# line_sensor.net
KiCad netlist of a schematic drawn in EAGLE
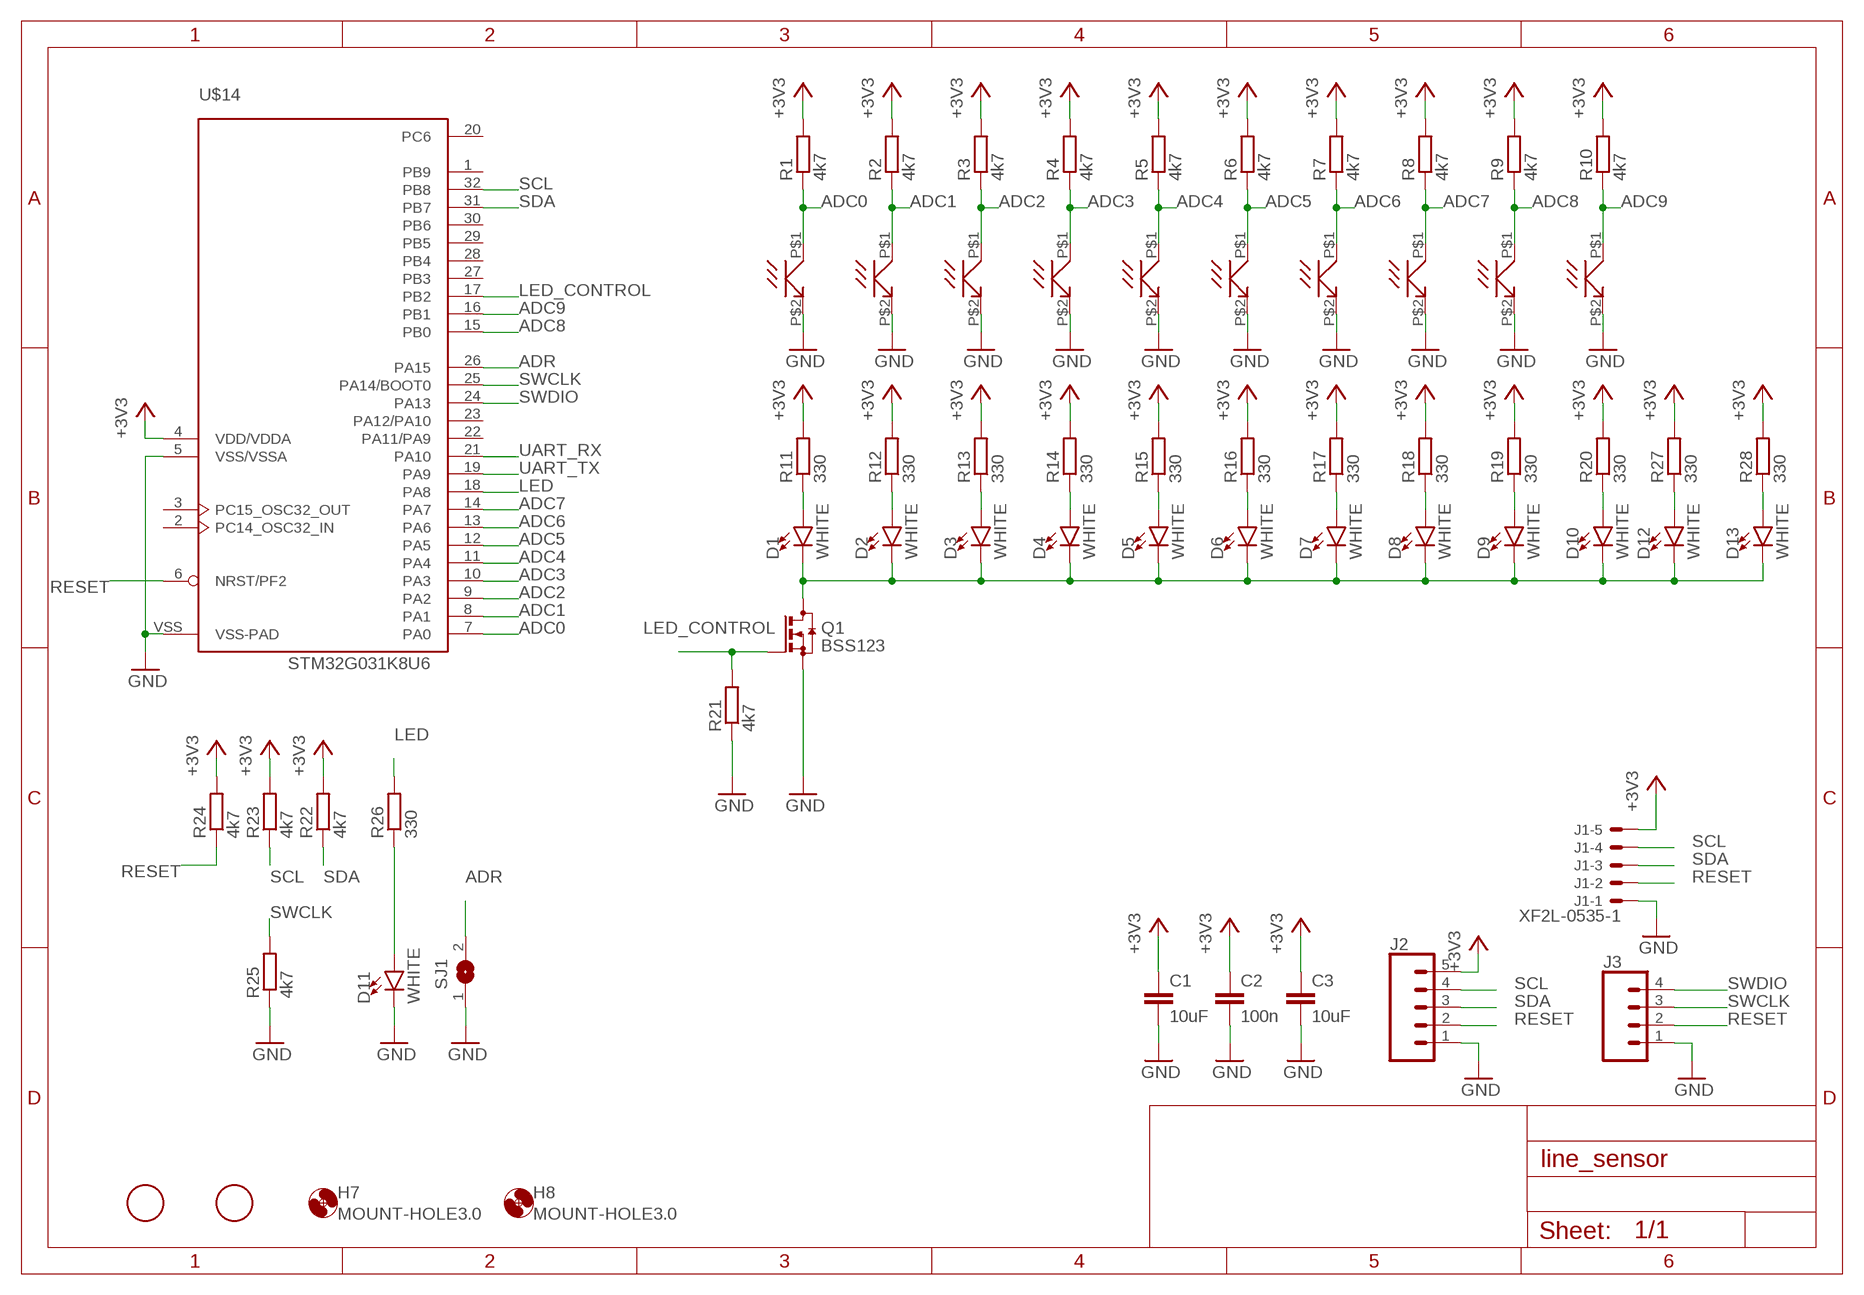
[diagram p0: schematic, sheet 1]

(export (version "E")
  (design (tool "Eeschema 10.0.6"))
  (components
    (comp (ref "C1")
      (value "10uF")
      (footprint "eagle-import:C0805K")
      (libsource (lib "eagle-import") (part "C-EUC0805K"))
    )
    (comp (ref "C2")
      (value "100n")
      (footprint "eagle-import:C0805K")
      (libsource (lib "eagle-import") (part "C-EUC0805K"))
    )
    (comp (ref "C3")
      (value "10uF")
      (footprint "eagle-import:C0805K")
      (libsource (lib "eagle-import") (part "C-EUC0805K"))
    )
    (comp (ref "D1")
      (value "WHITE")
      (footprint "eagle-import:LED-1206")
      (libsource (lib "eagle-import") (part "LED-WHITE1206"))
    )
    (comp (ref "D2")
      (value "WHITE")
      (footprint "eagle-import:LED-1206")
      (libsource (lib "eagle-import") (part "LED-WHITE1206"))
    )
    (comp (ref "D3")
      (value "WHITE")
      (footprint "eagle-import:LED-1206")
      (libsource (lib "eagle-import") (part "LED-WHITE1206"))
    )
    (comp (ref "D4")
      (value "WHITE")
      (footprint "eagle-import:LED-1206")
      (libsource (lib "eagle-import") (part "LED-WHITE1206"))
    )
    (comp (ref "D5")
      (value "WHITE")
      (footprint "eagle-import:LED-1206")
      (libsource (lib "eagle-import") (part "LED-WHITE1206"))
    )
    (comp (ref "D6")
      (value "WHITE")
      (footprint "eagle-import:LED-1206")
      (libsource (lib "eagle-import") (part "LED-WHITE1206"))
    )
    (comp (ref "D7")
      (value "WHITE")
      (footprint "eagle-import:LED-1206")
      (libsource (lib "eagle-import") (part "LED-WHITE1206"))
    )
    (comp (ref "D8")
      (value "WHITE")
      (footprint "eagle-import:LED-1206")
      (libsource (lib "eagle-import") (part "LED-WHITE1206"))
    )
    (comp (ref "D9")
      (value "WHITE")
      (footprint "eagle-import:LED-1206")
      (libsource (lib "eagle-import") (part "LED-WHITE1206"))
    )
    (comp (ref "D10")
      (value "WHITE")
      (footprint "eagle-import:LED-1206")
      (libsource (lib "eagle-import") (part "LED-WHITE1206"))
    )
    (comp (ref "D11")
      (value "WHITE")
      (footprint "eagle-import:LED-1206")
      (libsource (lib "eagle-import") (part "LED-WHITE1206"))
    )
    (comp (ref "D12")
      (value "WHITE")
      (footprint "eagle-import:LED-1206")
      (libsource (lib "eagle-import") (part "LED-WHITE1206"))
    )
    (comp (ref "D13")
      (value "WHITE")
      (footprint "eagle-import:LED-1206")
      (libsource (lib "eagle-import") (part "LED-WHITE1206"))
    )
    (comp (ref "H7")
      (value "MOUNT-HOLE3.0")
      (footprint "eagle-import:3,0")
      (libsource (lib "eagle-import") (part "MOUNT-HOLE3.0"))
    )
    (comp (ref "H8")
      (value "MOUNT-HOLE3.0")
      (footprint "eagle-import:3,0")
      (libsource (lib "eagle-import") (part "MOUNT-HOLE3.0"))
    )
    (comp (ref "J1")
      (value "XF2L-0535-1")
      (footprint "eagle-import:XF2L-0535-1")
      (fields (field (name "MPN") "XF2L-0535-1A"))
      (libsource (lib "eagle-import") (part "XF2-05?35-1L"))
    )
    (comp (ref "J2")
      (value "CONN_05")
      (footprint "eagle-import:1X05")
      (libsource (lib "eagle-import") (part "CONN_05"))
    )
    (comp (ref "J3")
      (value "CONN_04LOCK")
      (footprint "eagle-import:1X04_LOCK")
      (libsource (lib "eagle-import") (part "CONN_04LOCK"))
    )
    (comp (ref "Q1")
      (value "BSS123")
      (footprint "eagle-import:SOT23")
      (libsource (lib "eagle-import") (part "BSS123"))
    )
    (comp (ref "R1")
      (value "4k7")
      (footprint "eagle-import:M0805")
      (libsource (lib "eagle-import") (part "R-EU_M0805"))
    )
    (comp (ref "R2")
      (value "4k7")
      (footprint "eagle-import:M0805")
      (libsource (lib "eagle-import") (part "R-EU_M0805"))
    )
    (comp (ref "R3")
      (value "4k7")
      (footprint "eagle-import:M0805")
      (libsource (lib "eagle-import") (part "R-EU_M0805"))
    )
    (comp (ref "R4")
      (value "4k7")
      (footprint "eagle-import:M0805")
      (libsource (lib "eagle-import") (part "R-EU_M0805"))
    )
    (comp (ref "R5")
      (value "4k7")
      (footprint "eagle-import:M0805")
      (libsource (lib "eagle-import") (part "R-EU_M0805"))
    )
    (comp (ref "R6")
      (value "4k7")
      (footprint "eagle-import:M0805")
      (libsource (lib "eagle-import") (part "R-EU_M0805"))
    )
    (comp (ref "R7")
      (value "4k7")
      (footprint "eagle-import:M0805")
      (libsource (lib "eagle-import") (part "R-EU_M0805"))
    )
    (comp (ref "R8")
      (value "4k7")
      (footprint "eagle-import:M0805")
      (libsource (lib "eagle-import") (part "R-EU_M0805"))
    )
    (comp (ref "R9")
      (value "4k7")
      (footprint "eagle-import:M0805")
      (libsource (lib "eagle-import") (part "R-EU_M0805"))
    )
    (comp (ref "R10")
      (value "4k7")
      (footprint "eagle-import:M0805")
      (libsource (lib "eagle-import") (part "R-EU_M0805"))
    )
    (comp (ref "R11")
      (value "330")
      (footprint "eagle-import:M0805")
      (libsource (lib "eagle-import") (part "R-EU_M0805"))
    )
    (comp (ref "R12")
      (value "330")
      (footprint "eagle-import:M0805")
      (libsource (lib "eagle-import") (part "R-EU_M0805"))
    )
    (comp (ref "R13")
      (value "330")
      (footprint "eagle-import:M0805")
      (libsource (lib "eagle-import") (part "R-EU_M0805"))
    )
    (comp (ref "R14")
      (value "330")
      (footprint "eagle-import:M0805")
      (libsource (lib "eagle-import") (part "R-EU_M0805"))
    )
    (comp (ref "R15")
      (value "330")
      (footprint "eagle-import:M0805")
      (libsource (lib "eagle-import") (part "R-EU_M0805"))
    )
    (comp (ref "R16")
      (value "330")
      (footprint "eagle-import:M0805")
      (libsource (lib "eagle-import") (part "R-EU_M0805"))
    )
    (comp (ref "R17")
      (value "330")
      (footprint "eagle-import:M0805")
      (libsource (lib "eagle-import") (part "R-EU_M0805"))
    )
    (comp (ref "R18")
      (value "330")
      (footprint "eagle-import:M0805")
      (libsource (lib "eagle-import") (part "R-EU_M0805"))
    )
    (comp (ref "R19")
      (value "330")
      (footprint "eagle-import:M0805")
      (libsource (lib "eagle-import") (part "R-EU_M0805"))
    )
    (comp (ref "R20")
      (value "330")
      (footprint "eagle-import:M0805")
      (libsource (lib "eagle-import") (part "R-EU_M0805"))
    )
    (comp (ref "R21")
      (value "4k7")
      (footprint "eagle-import:M0805")
      (libsource (lib "eagle-import") (part "R-EU_M0805"))
    )
    (comp (ref "R22")
      (value "4k7")
      (footprint "eagle-import:M0805")
      (libsource (lib "eagle-import") (part "R-EU_M0805"))
    )
    (comp (ref "R23")
      (value "4k7")
      (footprint "eagle-import:M0805")
      (libsource (lib "eagle-import") (part "R-EU_M0805"))
    )
    (comp (ref "R24")
      (value "4k7")
      (footprint "eagle-import:M0805")
      (libsource (lib "eagle-import") (part "R-EU_M0805"))
    )
    (comp (ref "R25")
      (value "4k7")
      (footprint "eagle-import:M0805")
      (libsource (lib "eagle-import") (part "R-EU_M0805"))
    )
    (comp (ref "R26")
      (value "330")
      (footprint "eagle-import:M0805")
      (libsource (lib "eagle-import") (part "R-EU_M0805"))
    )
    (comp (ref "R27")
      (value "330")
      (footprint "eagle-import:M0805")
      (libsource (lib "eagle-import") (part "R-EU_M0805"))
    )
    (comp (ref "R28")
      (value "330")
      (footprint "eagle-import:M0805")
      (libsource (lib "eagle-import") (part "R-EU_M0805"))
    )
    (comp (ref "SJ1") (value "SJ") (footprint "eagle-import:SJ") (libsource (lib "eagle-import") (part "SJ")))
    (comp (ref "U$1")
      (value "SFH3710")
      (footprint "eagle-import:SFH710")
      (libsource (lib "eagle-import") (part "SFH3710"))
    )
    (comp (ref "U$2")
      (value "SFH3710")
      (footprint "eagle-import:SFH710")
      (libsource (lib "eagle-import") (part "SFH3710"))
    )
    (comp (ref "U$3")
      (value "SFH3710")
      (footprint "eagle-import:SFH710")
      (libsource (lib "eagle-import") (part "SFH3710"))
    )
    (comp (ref "U$4")
      (value "SFH3710")
      (footprint "eagle-import:SFH710")
      (libsource (lib "eagle-import") (part "SFH3710"))
    )
    (comp (ref "U$5")
      (value "SFH3710")
      (footprint "eagle-import:SFH710")
      (libsource (lib "eagle-import") (part "SFH3710"))
    )
    (comp (ref "U$6")
      (value "SFH3710")
      (footprint "eagle-import:SFH710")
      (libsource (lib "eagle-import") (part "SFH3710"))
    )
    (comp (ref "U$7")
      (value "SFH3710")
      (footprint "eagle-import:SFH710")
      (libsource (lib "eagle-import") (part "SFH3710"))
    )
    (comp (ref "U$8")
      (value "SFH3710")
      (footprint "eagle-import:SFH710")
      (libsource (lib "eagle-import") (part "SFH3710"))
    )
    (comp (ref "U$9")
      (value "SFH3710")
      (footprint "eagle-import:SFH710")
      (libsource (lib "eagle-import") (part "SFH3710"))
    )
    (comp (ref "U$10")
      (value "SFH3710")
      (footprint "eagle-import:SFH710")
      (libsource (lib "eagle-import") (part "SFH3710"))
    )
    (comp (ref "U$12")
      (value "FIDUCIAL")
      (footprint "eagle-import:FIDUCIAL_1MM")
      (libsource (lib "eagle-import") (part "FIDUCIAL"))
    )
    (comp (ref "U$13")
      (value "FIDUCIAL")
      (footprint "eagle-import:FIDUCIAL_1MM")
      (libsource (lib "eagle-import") (part "FIDUCIAL"))
    )
    (comp (ref "U$14")
      (value "STM32G031K8U6")
      (footprint "eagle-import:UFQFPN32")
      (libsource (lib "eagle-import") (part "STM32G031K8U6"))
    )
  )
  (nets
    (net (code "1") (name "+3V3") (class "Default")
      (node (ref "C1") (pin "1") (pinfunction "1_1") (pintype "passive"))
      (node (ref "C2") (pin "1") (pinfunction "1_1") (pintype "passive"))
      (node (ref "C3") (pin "1") (pinfunction "1_1") (pintype "passive"))
      (node (ref "J1") (pin "5") (pinfunction "MS_5") (pintype "passive"))
      (node (ref "J2") (pin "5") (pinfunction "5_5") (pintype "passive"))
      (node (ref "R1") (pin "2") (pinfunction "2_2") (pintype "passive"))
      (node (ref "R10") (pin "2") (pinfunction "2_2") (pintype "passive"))
      (node (ref "R11") (pin "2") (pinfunction "2_2") (pintype "passive"))
      (node (ref "R12") (pin "2") (pinfunction "2_2") (pintype "passive"))
      (node (ref "R13") (pin "2") (pinfunction "2_2") (pintype "passive"))
      (node (ref "R14") (pin "2") (pinfunction "2_2") (pintype "passive"))
      (node (ref "R15") (pin "2") (pinfunction "2_2") (pintype "passive"))
      (node (ref "R16") (pin "2") (pinfunction "2_2") (pintype "passive"))
      (node (ref "R17") (pin "2") (pinfunction "2_2") (pintype "passive"))
      (node (ref "R18") (pin "2") (pinfunction "2_2") (pintype "passive"))
      (node (ref "R19") (pin "2") (pinfunction "2_2") (pintype "passive"))
      (node (ref "R2") (pin "2") (pinfunction "2_2") (pintype "passive"))
      (node (ref "R20") (pin "2") (pinfunction "2_2") (pintype "passive"))
      (node (ref "R22") (pin "2") (pinfunction "2_2") (pintype "passive"))
      (node (ref "R23") (pin "2") (pinfunction "2_2") (pintype "passive"))
      (node (ref "R24") (pin "2") (pinfunction "2_2") (pintype "passive"))
      (node (ref "R27") (pin "2") (pinfunction "2_2") (pintype "passive"))
      (node (ref "R28") (pin "2") (pinfunction "2_2") (pintype "passive"))
      (node (ref "R3") (pin "2") (pinfunction "2_2") (pintype "passive"))
      (node (ref "R4") (pin "2") (pinfunction "2_2") (pintype "passive"))
      (node (ref "R5") (pin "2") (pinfunction "2_2") (pintype "passive"))
      (node (ref "R6") (pin "2") (pinfunction "2_2") (pintype "passive"))
      (node (ref "R7") (pin "2") (pinfunction "2_2") (pintype "passive"))
      (node (ref "R8") (pin "2") (pinfunction "2_2") (pintype "passive"))
      (node (ref "R9") (pin "2") (pinfunction "2_2") (pintype "passive"))
      (node (ref "U$14") (pin "4") (pinfunction "VDD/VDDA_4") (pintype "power_in"))
    )
    (net (code "2") (name "/ADC0") (class "Default")
      (node (ref "R1") (pin "1") (pinfunction "1_1") (pintype "passive"))
      (node (ref "U$1") (pin "P$1") (pinfunction "C_P$1") (pintype "bidirectional"))
      (node (ref "U$14") (pin "7") (pinfunction "PA0_7") (pintype "bidirectional"))
    )
    (net (code "3") (name "/ADC1") (class "Default")
      (node (ref "R2") (pin "1") (pinfunction "1_1") (pintype "passive"))
      (node (ref "U$14") (pin "8") (pinfunction "PA1_8") (pintype "bidirectional"))
      (node (ref "U$2") (pin "P$1") (pinfunction "C_P$1") (pintype "bidirectional"))
    )
    (net (code "4") (name "/ADC2") (class "Default")
      (node (ref "R3") (pin "1") (pinfunction "1_1") (pintype "passive"))
      (node (ref "U$14") (pin "9") (pinfunction "PA2_9") (pintype "bidirectional"))
      (node (ref "U$3") (pin "P$1") (pinfunction "C_P$1") (pintype "bidirectional"))
    )
    (net (code "5") (name "/ADC3") (class "Default")
      (node (ref "R4") (pin "1") (pinfunction "1_1") (pintype "passive"))
      (node (ref "U$14") (pin "10") (pinfunction "PA3_10") (pintype "bidirectional"))
      (node (ref "U$4") (pin "P$1") (pinfunction "C_P$1") (pintype "bidirectional"))
    )
    (net (code "6") (name "/ADC4") (class "Default")
      (node (ref "R5") (pin "1") (pinfunction "1_1") (pintype "passive"))
      (node (ref "U$14") (pin "11") (pinfunction "PA4_11") (pintype "bidirectional"))
      (node (ref "U$5") (pin "P$1") (pinfunction "C_P$1") (pintype "bidirectional"))
    )
    (net (code "7") (name "/ADC5") (class "Default")
      (node (ref "R6") (pin "1") (pinfunction "1_1") (pintype "passive"))
      (node (ref "U$14") (pin "12") (pinfunction "PA5_12") (pintype "bidirectional"))
      (node (ref "U$6") (pin "P$1") (pinfunction "C_P$1") (pintype "bidirectional"))
    )
    (net (code "8") (name "/ADC6") (class "Default")
      (node (ref "R7") (pin "1") (pinfunction "1_1") (pintype "passive"))
      (node (ref "U$14") (pin "13") (pinfunction "PA6_13") (pintype "bidirectional"))
      (node (ref "U$7") (pin "P$1") (pinfunction "C_P$1") (pintype "bidirectional"))
    )
    (net (code "9") (name "/ADC7") (class "Default")
      (node (ref "R8") (pin "1") (pinfunction "1_1") (pintype "passive"))
      (node (ref "U$14") (pin "14") (pinfunction "PA7_14") (pintype "bidirectional"))
      (node (ref "U$8") (pin "P$1") (pinfunction "C_P$1") (pintype "bidirectional"))
    )
    (net (code "10") (name "/ADC8") (class "Default")
      (node (ref "R9") (pin "1") (pinfunction "1_1") (pintype "passive"))
      (node (ref "U$14") (pin "15") (pinfunction "PB0_15") (pintype "bidirectional"))
      (node (ref "U$9") (pin "P$1") (pinfunction "C_P$1") (pintype "bidirectional"))
    )
    (net (code "11") (name "/ADC9") (class "Default")
      (node (ref "R10") (pin "1") (pinfunction "1_1") (pintype "passive"))
      (node (ref "U$10") (pin "P$1") (pinfunction "C_P$1") (pintype "bidirectional"))
      (node (ref "U$14") (pin "16") (pinfunction "PB1_16") (pintype "bidirectional"))
    )
    (net (code "12") (name "/ADR") (class "Default")
      (node (ref "SJ1") (pin "2") (pinfunction "2_2") (pintype "passive"))
      (node (ref "U$14") (pin "26") (pinfunction "PA15_26") (pintype "bidirectional"))
    )
    (net (code "13") (name "/LED") (class "Default")
      (node (ref "R26") (pin "2") (pinfunction "2_2") (pintype "passive"))
      (node (ref "U$14") (pin "18") (pinfunction "PA8_18") (pintype "bidirectional"))
    )
    (net (code "14") (name "/LED_CONTROL") (class "Default")
      (node (ref "Q1") (pin "1") (pinfunction "G_1") (pintype "passive"))
      (node (ref "R21") (pin "2") (pinfunction "2_2") (pintype "passive"))
      (node (ref "U$14") (pin "17") (pinfunction "PB2_17") (pintype "bidirectional"))
    )
    (net (code "15") (name "/RESET") (class "Default")
      (node (ref "J1") (pin "2") (pinfunction "MS_2") (pintype "passive"))
      (node (ref "J2") (pin "2") (pinfunction "2_2") (pintype "passive"))
      (node (ref "J3") (pin "2") (pinfunction "2_2") (pintype "passive"))
      (node (ref "R24") (pin "1") (pinfunction "1_1") (pintype "passive"))
      (node (ref "U$14") (pin "6") (pinfunction "NRST/PF2_6") (pintype "bidirectional"))
    )
    (net (code "16") (name "/SCL") (class "Default")
      (node (ref "J1") (pin "4") (pinfunction "MS_4") (pintype "passive"))
      (node (ref "J2") (pin "4") (pinfunction "4_4") (pintype "passive"))
      (node (ref "R23") (pin "1") (pinfunction "1_1") (pintype "passive"))
      (node (ref "U$14") (pin "32") (pinfunction "PB8_32") (pintype "bidirectional"))
    )
    (net (code "17") (name "/SDA") (class "Default")
      (node (ref "J1") (pin "3") (pinfunction "MS_3") (pintype "passive"))
      (node (ref "J2") (pin "3") (pinfunction "3_3") (pintype "passive"))
      (node (ref "R22") (pin "1") (pinfunction "1_1") (pintype "passive"))
      (node (ref "U$14") (pin "31") (pinfunction "PB7_31") (pintype "bidirectional"))
    )
    (net (code "18") (name "/SWCLK") (class "Default")
      (node (ref "J3") (pin "3") (pinfunction "3_3") (pintype "passive"))
      (node (ref "R25") (pin "2") (pinfunction "2_2") (pintype "passive"))
      (node (ref "U$14") (pin "25") (pinfunction "PA14/BOOT0_25") (pintype "bidirectional"))
    )
    (net (code "19") (name "/SWDIO") (class "Default")
      (node (ref "J3") (pin "4") (pinfunction "4_4") (pintype "passive"))
      (node (ref "U$14") (pin "24") (pinfunction "PA13_24") (pintype "bidirectional"))
    )
    (net (code "20") (name "/UART_RX") (class "Default")
      (node (ref "U$14") (pin "21") (pinfunction "PA10_21") (pintype "bidirectional"))
    )
    (net (code "21") (name "/UART_TX") (class "Default")
      (node (ref "U$14") (pin "19") (pinfunction "PA9_19") (pintype "bidirectional"))
    )
    (net (code "22") (name "GND") (class "Default")
      (node (ref "C1") (pin "2") (pinfunction "2_2") (pintype "passive"))
      (node (ref "C2") (pin "2") (pinfunction "2_2") (pintype "passive"))
      (node (ref "C3") (pin "2") (pinfunction "2_2") (pintype "passive"))
      (node (ref "D11") (pin "C") (pinfunction "C_C") (pintype "passive"))
      (node (ref "J1") (pin "1") (pinfunction "MSV_1") (pintype "passive"))
      (node (ref "J2") (pin "1") (pinfunction "1_1") (pintype "passive"))
      (node (ref "J3") (pin "1") (pinfunction "1_1") (pintype "passive"))
      (node (ref "Q1") (pin "2") (pinfunction "S_2") (pintype "passive"))
      (node (ref "R21") (pin "1") (pinfunction "1_1") (pintype "passive"))
      (node (ref "R25") (pin "1") (pinfunction "1_1") (pintype "passive"))
      (node (ref "SJ1") (pin "1") (pinfunction "1_1") (pintype "passive"))
      (node (ref "U$1") (pin "P$2") (pinfunction "E_P$2") (pintype "bidirectional"))
      (node (ref "U$10") (pin "P$2") (pinfunction "E_P$2") (pintype "bidirectional"))
      (node (ref "U$14") (pin "5") (pinfunction "VSS/VSSA_5") (pintype "power_in"))
      (node (ref "U$14") (pin "VSS") (pinfunction "VSS-PAD_VSS") (pintype "bidirectional"))
      (node (ref "U$2") (pin "P$2") (pinfunction "E_P$2") (pintype "bidirectional"))
      (node (ref "U$3") (pin "P$2") (pinfunction "E_P$2") (pintype "bidirectional"))
      (node (ref "U$4") (pin "P$2") (pinfunction "E_P$2") (pintype "bidirectional"))
      (node (ref "U$5") (pin "P$2") (pinfunction "E_P$2") (pintype "bidirectional"))
      (node (ref "U$6") (pin "P$2") (pinfunction "E_P$2") (pintype "bidirectional"))
      (node (ref "U$7") (pin "P$2") (pinfunction "E_P$2") (pintype "bidirectional"))
      (node (ref "U$8") (pin "P$2") (pinfunction "E_P$2") (pintype "bidirectional"))
      (node (ref "U$9") (pin "P$2") (pinfunction "E_P$2") (pintype "bidirectional"))
    )
    (net (code "23") (name "Net-(D1-PadA)") (class "Default")
      (node (ref "D1") (pin "A") (pinfunction "A_A") (pintype "passive"))
      (node (ref "R11") (pin "1") (pinfunction "1_1") (pintype "passive"))
    )
    (net (code "24") (name "Net-(D2-PadA)") (class "Default")
      (node (ref "D2") (pin "A") (pinfunction "A_A") (pintype "passive"))
      (node (ref "R12") (pin "1") (pinfunction "1_1") (pintype "passive"))
    )
    (net (code "25") (name "Net-(D3-PadA)") (class "Default")
      (node (ref "D3") (pin "A") (pinfunction "A_A") (pintype "passive"))
      (node (ref "R13") (pin "1") (pinfunction "1_1") (pintype "passive"))
    )
    (net (code "26") (name "Net-(D4-PadA)") (class "Default")
      (node (ref "D4") (pin "A") (pinfunction "A_A") (pintype "passive"))
      (node (ref "R14") (pin "1") (pinfunction "1_1") (pintype "passive"))
    )
    (net (code "27") (name "Net-(D5-PadA)") (class "Default")
      (node (ref "D5") (pin "A") (pinfunction "A_A") (pintype "passive"))
      (node (ref "R15") (pin "1") (pinfunction "1_1") (pintype "passive"))
    )
    (net (code "28") (name "Net-(D6-PadA)") (class "Default")
      (node (ref "D6") (pin "A") (pinfunction "A_A") (pintype "passive"))
      (node (ref "R16") (pin "1") (pinfunction "1_1") (pintype "passive"))
    )
    (net (code "29") (name "Net-(D7-PadA)") (class "Default")
      (node (ref "D7") (pin "A") (pinfunction "A_A") (pintype "passive"))
      (node (ref "R17") (pin "1") (pinfunction "1_1") (pintype "passive"))
    )
    (net (code "30") (name "Net-(D8-PadA)") (class "Default")
      (node (ref "D8") (pin "A") (pinfunction "A_A") (pintype "passive"))
      (node (ref "R18") (pin "1") (pinfunction "1_1") (pintype "passive"))
    )
    (net (code "31") (name "Net-(D9-PadA)") (class "Default")
      (node (ref "D9") (pin "A") (pinfunction "A_A") (pintype "passive"))
      (node (ref "R19") (pin "1") (pinfunction "1_1") (pintype "passive"))
    )
    (net (code "32") (name "Net-(D10-PadA)") (class "Default")
      (node (ref "D10") (pin "A") (pinfunction "A_A") (pintype "passive"))
      (node (ref "R20") (pin "1") (pinfunction "1_1") (pintype "passive"))
    )
    (net (code "33") (name "Net-(D11-PadA)") (class "Default")
      (node (ref "D11") (pin "A") (pinfunction "A_A") (pintype "passive"))
      (node (ref "R26") (pin "1") (pinfunction "1_1") (pintype "passive"))
    )
    (net (code "34") (name "Net-(D12-PadA)") (class "Default")
      (node (ref "D12") (pin "A") (pinfunction "A_A") (pintype "passive"))
      (node (ref "R27") (pin "1") (pinfunction "1_1") (pintype "passive"))
    )
    (net (code "35") (name "Net-(D13-PadA)") (class "Default")
      (node (ref "D13") (pin "A") (pinfunction "A_A") (pintype "passive"))
      (node (ref "R28") (pin "1") (pinfunction "1_1") (pintype "passive"))
    )
    (net (code "36") (name "Net-(Q1-D)") (class "Default")
      (node (ref "D1") (pin "C") (pinfunction "C_C") (pintype "passive"))
      (node (ref "D10") (pin "C") (pinfunction "C_C") (pintype "passive"))
      (node (ref "D12") (pin "C") (pinfunction "C_C") (pintype "passive"))
      (node (ref "D13") (pin "C") (pinfunction "C_C") (pintype "passive"))
      (node (ref "D2") (pin "C") (pinfunction "C_C") (pintype "passive"))
      (node (ref "D3") (pin "C") (pinfunction "C_C") (pintype "passive"))
      (node (ref "D4") (pin "C") (pinfunction "C_C") (pintype "passive"))
      (node (ref "D5") (pin "C") (pinfunction "C_C") (pintype "passive"))
      (node (ref "D6") (pin "C") (pinfunction "C_C") (pintype "passive"))
      (node (ref "D7") (pin "C") (pinfunction "C_C") (pintype "passive"))
      (node (ref "D8") (pin "C") (pinfunction "C_C") (pintype "passive"))
      (node (ref "D9") (pin "C") (pinfunction "C_C") (pintype "passive"))
      (node (ref "Q1") (pin "3") (pinfunction "D_3") (pintype "passive"))
    )
    (net (code "37") (name "unconnected-(U$14-PA11{slash}PA9-Pad22)") (class "Default")
      (node (ref "U$14") (pin "22") (pinfunction "PA11/PA9_22") (pintype "bidirectional"))
    )
    (net (code "38") (name "unconnected-(U$14-PA12{slash}PA10-Pad23)") (class "Default")
      (node (ref "U$14") (pin "23") (pinfunction "PA12/PA10_23") (pintype "bidirectional"))
    )
    (net (code "39") (name "unconnected-(U$14-PB3-Pad27)") (class "Default")
      (node (ref "U$14") (pin "27") (pinfunction "PB3_27") (pintype "bidirectional"))
    )
    (net (code "40") (name "unconnected-(U$14-PB4-Pad28)") (class "Default")
      (node (ref "U$14") (pin "28") (pinfunction "PB4_28") (pintype "bidirectional"))
    )
    (net (code "41") (name "unconnected-(U$14-PB5-Pad29)") (class "Default")
      (node (ref "U$14") (pin "29") (pinfunction "PB5_29") (pintype "bidirectional"))
    )
    (net (code "42") (name "unconnected-(U$14-PB6-Pad30)") (class "Default")
      (node (ref "U$14") (pin "30") (pinfunction "PB6_30") (pintype "bidirectional"))
    )
    (net (code "43") (name "unconnected-(U$14-PB9-Pad1)") (class "Default")
      (node (ref "U$14") (pin "1") (pinfunction "PB9_1") (pintype "bidirectional"))
    )
    (net (code "44") (name "unconnected-(U$14-PC6-Pad20)") (class "Default")
      (node (ref "U$14") (pin "20") (pinfunction "PC6_20") (pintype "bidirectional"))
    )
    (net (code "45") (name "unconnected-(U$14-PC14_OSC32_IN-Pad2)") (class "Default")
      (node (ref "U$14") (pin "2") (pinfunction "PC14_OSC32_IN_2") (pintype "bidirectional"))
    )
    (net (code "46") (name "unconnected-(U$14-PC15_OSC32_OUT-Pad3)") (class "Default")
      (node (ref "U$14") (pin "3") (pinfunction "PC15_OSC32_OUT_3") (pintype "bidirectional"))
    )
  )
)
